# mintyboostv3_SingleSidedDIY.net
KiCad netlist of a schematic drawn in EAGLE
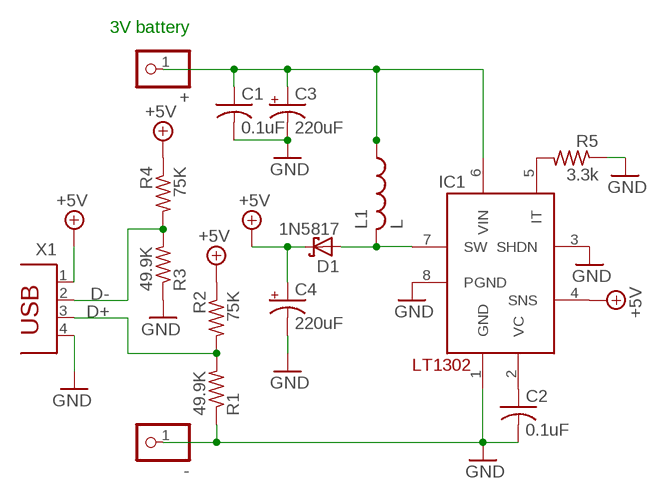
[diagram p0: schematic, sheet 1]

(export (version "E")
  (design (tool "Eeschema 10.0.6"))
  (components
    (comp (ref "+")
      (value "PINHD-1X1")
      (footprint "eagle-import:1X01")
      (libsource (lib "eagle-import") (part "PINHD-1X1"))
    )
    (comp (ref "-")
      (value "PINHD-1X1")
      (footprint "eagle-import:1X01")
      (libsource (lib "eagle-import") (part "PINHD-1X1"))
    )
    (comp (ref "C1")
      (value "0.1uF")
      (footprint "eagle-import:C025-025X050")
      (libsource (lib "eagle-import") (part "C-US025-025X050"))
    )
    (comp (ref "C2")
      (value "0.1uF")
      (footprint "eagle-import:C025-025X050")
      (libsource (lib "eagle-import") (part "C-US025-025X050"))
    )
    (comp (ref "C3")
      (value "220uF")
      (footprint "eagle-import:E2,5-5")
      (libsource (lib "eagle-import") (part "CPOL-USE2.5-5"))
    )
    (comp (ref "C4")
      (value "220uF")
      (footprint "eagle-import:E2,5-5")
      (libsource (lib "eagle-import") (part "CPOL-USE2.5-5"))
    )
    (comp (ref "D1")
      (value "1N5817")
      (footprint "eagle-import:DO41-7")
      (libsource (lib "eagle-import") (part "SCHOTTKY-DIODEDO41-7"))
    )
    (comp (ref "IC1")
      (value "LT1302")
      (footprint "eagle-import:DIL08")
      (libsource (lib "eagle-import") (part "LT1302"))
    )
    (comp (ref "L1") (value "L") (footprint "eagle-import:6000") (libsource (lib "eagle-import") (part "L")))
    (comp (ref "R1")
      (value "49.9K")
      (footprint "eagle-import:0204_5")
      (libsource (lib "eagle-import") (part "R-US_0204/5"))
    )
    (comp (ref "R2")
      (value "75K")
      (footprint "eagle-import:0204_5")
      (libsource (lib "eagle-import") (part "R-US_0204/5"))
    )
    (comp (ref "R3")
      (value "49.9K")
      (footprint "eagle-import:0204_5")
      (libsource (lib "eagle-import") (part "R-US_0204/5"))
    )
    (comp (ref "R4")
      (value "75K")
      (footprint "eagle-import:0204_5")
      (libsource (lib "eagle-import") (part "R-US_0204/5"))
    )
    (comp (ref "R5")
      (value "3.3k")
      (footprint "eagle-import:0204_5")
      (libsource (lib "eagle-import") (part "R-US_0204/5"))
    )
    (comp (ref "X1")
      (value "PN87520")
      (footprint "eagle-import:PN87520")
      (libsource (lib "eagle-import") (part "PN87520"))
    )
  )
  (nets
    (net (code "1") (name "+5V") (class "Default")
      (node (ref "C4") (pin "+") (pinfunction "+_+") (pintype "passive"))
      (node (ref "D1") (pin "C") (pinfunction "C_C") (pintype "passive"))
      (node (ref "IC1") (pin "4") (pinfunction "SNS_4") (pintype "passive"))
      (node (ref "R2") (pin "1") (pinfunction "1_1") (pintype "passive"))
      (node (ref "R4") (pin "1") (pinfunction "1_1") (pintype "passive"))
      (node (ref "X1") (pin "1") (pinfunction "1_1") (pintype "bidirectional"))
    )
    (net (code "2") (name "/D+") (class "Default")
      (node (ref "R1") (pin "2") (pinfunction "2_2") (pintype "passive"))
      (node (ref "R2") (pin "2") (pinfunction "2_2") (pintype "passive"))
      (node (ref "X1") (pin "3") (pinfunction "3_3") (pintype "bidirectional"))
    )
    (net (code "3") (name "/D-") (class "Default")
      (node (ref "R3") (pin "2") (pinfunction "2_2") (pintype "passive"))
      (node (ref "R4") (pin "2") (pinfunction "2_2") (pintype "passive"))
      (node (ref "X1") (pin "2") (pinfunction "2_2") (pintype "bidirectional"))
    )
    (net (code "4") (name "GND") (class "Default")
      (node (ref "-") (pin "1") (pinfunction "1_1") (pintype "passive"))
      (node (ref "C1") (pin "2") (pinfunction "2_2") (pintype "passive"))
      (node (ref "C2") (pin "2") (pinfunction "2_2") (pintype "passive"))
      (node (ref "C3") (pin "-") (pinfunction "-_-") (pintype "passive"))
      (node (ref "C4") (pin "-") (pinfunction "-_-") (pintype "passive"))
      (node (ref "IC1") (pin "1") (pinfunction "GND_1") (pintype "input"))
      (node (ref "IC1") (pin "3") (pinfunction "SHDN_3") (pintype "input"))
      (node (ref "IC1") (pin "8") (pinfunction "PGND_8") (pintype "input"))
      (node (ref "R1") (pin "1") (pinfunction "1_1") (pintype "passive"))
      (node (ref "R3") (pin "1") (pinfunction "1_1") (pintype "passive"))
      (node (ref "R5") (pin "1") (pinfunction "1_1") (pintype "passive"))
      (node (ref "X1") (pin "4") (pinfunction "4_4") (pintype "bidirectional"))
    )
    (net (code "5") (name "Net-(IC1-IT)") (class "Default")
      (node (ref "IC1") (pin "5") (pinfunction "IT_5") (pintype "input"))
      (node (ref "R5") (pin "2") (pinfunction "2_2") (pintype "passive"))
    )
    (net (code "6") (name "Net-(IC1-SW)") (class "Default")
      (node (ref "D1") (pin "A") (pinfunction "A_A") (pintype "passive"))
      (node (ref "IC1") (pin "7") (pinfunction "SW_7") (pintype "input"))
      (node (ref "L1") (pin "2") (pinfunction "2_2") (pintype "passive"))
    )
    (net (code "7") (name "Net-(IC1-VC)") (class "Default")
      (node (ref "C2") (pin "1") (pinfunction "1_1") (pintype "passive"))
      (node (ref "IC1") (pin "2") (pinfunction "VC_2") (pintype "passive"))
    )
    (net (code "8") (name "Net-(IC1-VIN)") (class "Default")
      (node (ref "+") (pin "1") (pinfunction "1_1") (pintype "passive"))
      (node (ref "C1") (pin "1") (pinfunction "1_1") (pintype "passive"))
      (node (ref "C3") (pin "+") (pinfunction "+_+") (pintype "passive"))
      (node (ref "IC1") (pin "6") (pinfunction "VIN_6") (pintype "input"))
      (node (ref "L1") (pin "1") (pinfunction "1_1") (pintype "passive"))
    )
  )
)
